# atmega328p_dip28.net
KiCad netlist of a schematic drawn in EAGLE
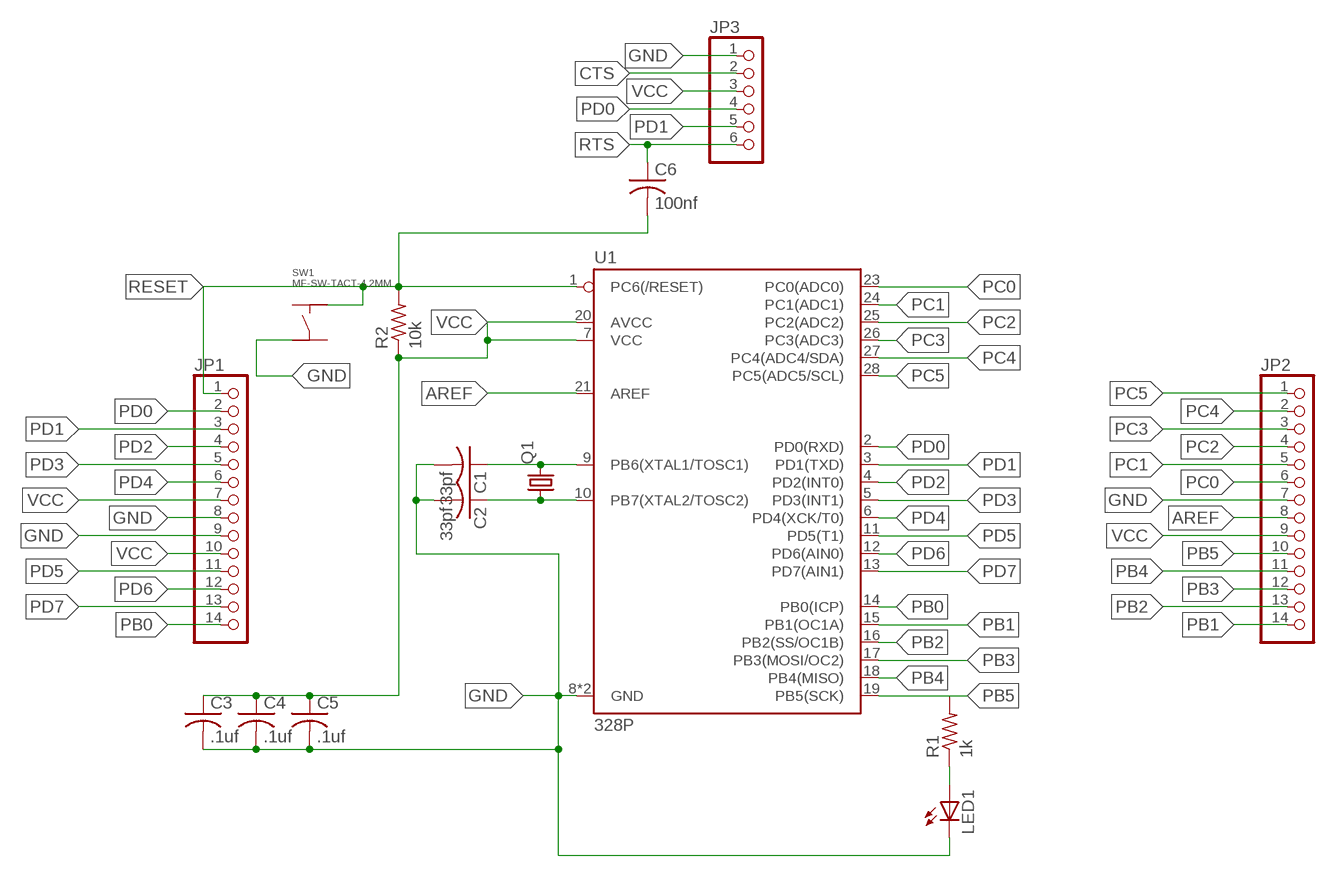
[diagram p0: schematic, sheet 1]

(export (version "E")
  (design (tool "Eeschema 10.0.6"))
  (components
    (comp (ref "C1")
      (value "33pf")
      (footprint "eagle-import:C0603K")
      (libsource (lib "eagle-import") (part "resistor_348_C-USC0603K"))
    )
    (comp (ref "C2")
      (value "33pf")
      (footprint "eagle-import:C0603K")
      (libsource (lib "eagle-import") (part "resistor_348_C-USC0603K"))
    )
    (comp (ref "C3")
      (value ".1uf")
      (footprint "eagle-import:C0603")
      (libsource (lib "eagle-import") (part "C-USC0603"))
    )
    (comp (ref "C4")
      (value ".1uf")
      (footprint "eagle-import:C0603")
      (libsource (lib "eagle-import") (part "C-USC0603"))
    )
    (comp (ref "C5")
      (value ".1uf")
      (footprint "eagle-import:C0603")
      (libsource (lib "eagle-import") (part "C-USC0603"))
    )
    (comp (ref "C6")
      (value "100nf")
      (footprint "eagle-import:C0603")
      (libsource (lib "eagle-import") (part "C-USC0603"))
    )
    (comp (ref "JP1")
      (value "PINHD-1X14-CB")
      (footprint "eagle-import:1X14-CB")
      (libsource (lib "eagle-import") (part "PINHD-1X14-CB"))
    )
    (comp (ref "JP2")
      (value "PINHD-1X14-CB")
      (footprint "eagle-import:1X14-CB")
      (libsource (lib "eagle-import") (part "PINHD-1X14-CB"))
    )
    (comp (ref "JP3")
      (value "PINHD-1X6")
      (footprint "eagle-import:1X06")
      (libsource (lib "eagle-import") (part "PINHD-1X6"))
    )
    (comp (ref "LED1")
      (value "LEDCHIP-LED0805")
      (footprint "eagle-import:CHIP-LED0805")
      (libsource (lib "eagle-import") (part "LEDCHIP-LED0805"))
    )
    (comp (ref "Q1")
      (value "CRYSTALCTS406")
      (footprint "eagle-import:CTS406")
      (libsource (lib "eagle-import") (part "CRYSTALCTS406"))
    )
    (comp (ref "R1")
      (value "1k")
      (footprint "eagle-import:R0603")
      (libsource (lib "eagle-import") (part "R-US_R0603"))
    )
    (comp (ref "R2")
      (value "10k")
      (footprint "eagle-import:R0603")
      (libsource (lib "eagle-import") (part "R-US_R0603"))
    )
    (comp (ref "SW1")
      (value "MF-SW-TACT-4.2MM")
      (footprint "eagle-import:MF_SWITCHES_TACT4.2MM")
      (fields (field (name "HOUSEPART") "YES"))
      (libsource (lib "eagle-import") (part "MF_SWITCHES_TACT_4.2MM"))
    )
    (comp (ref "U1")
      (value "328P")
      (footprint "eagle-import:DIP28")
      (libsource (lib "eagle-import") (part "ATMEGA328P_PDIP"))
    )
  )
  (nets
    (net (code "1") (name "AREF") (class "Default")
      (node (ref "JP2") (pin "8") (pinfunction "8_8") (pintype "passive"))
      (node (ref "U1") (pin "21") (pinfunction "AREF_21") (pintype "bidirectional"))
    )
    (net (code "2") (name "CTS") (class "Default")
      (node (ref "JP3") (pin "2") (pinfunction "2_2") (pintype "passive"))
    )
    (net (code "3") (name "GND") (class "Default")
      (node (ref "C1") (pin "2") (pinfunction "2_2") (pintype "passive"))
      (node (ref "C2") (pin "2") (pinfunction "2_2") (pintype "passive"))
      (node (ref "C3") (pin "2") (pinfunction "2_2") (pintype "passive"))
      (node (ref "C4") (pin "2") (pinfunction "2_2") (pintype "passive"))
      (node (ref "C5") (pin "2") (pinfunction "2_2") (pintype "passive"))
      (node (ref "JP1") (pin "8") (pinfunction "8_8") (pintype "passive"))
      (node (ref "JP1") (pin "9") (pinfunction "9_9") (pintype "passive"))
      (node (ref "JP2") (pin "7") (pinfunction "7_7") (pintype "passive"))
      (node (ref "JP3") (pin "1") (pinfunction "1_1") (pintype "passive"))
      (node (ref "LED1") (pin "C") (pinfunction "C_C") (pintype "passive"))
      (node (ref "SW1") (pin "P$3") (pinfunction "P$3_P$3") (pintype "bidirectional"))
      (node (ref "U1") (pin "22") (pinfunction "GND_22") (pintype "bidirectional"))
      (node (ref "U1") (pin "8") (pinfunction "GND_8") (pintype "bidirectional"))
    )
    (net (code "4") (name "Net-(LED1-PadA)") (class "Default")
      (node (ref "LED1") (pin "A") (pinfunction "A_A") (pintype "passive"))
      (node (ref "R1") (pin "1") (pinfunction "1_1") (pintype "passive"))
    )
    (net (code "5") (name "Net-(Q1-2)") (class "Default")
      (node (ref "C1") (pin "1") (pinfunction "1_1") (pintype "passive"))
      (node (ref "Q1") (pin "3") (pinfunction "2_3") (pintype "passive"))
      (node (ref "U1") (pin "9") (pinfunction "PB6(XTAL1/TOSC1)_9") (pintype "bidirectional"))
    )
    (net (code "6") (name "Net-(U1-PB7(XTAL2{slash}TOSC2))") (class "Default")
      (node (ref "C2") (pin "1") (pinfunction "1_1") (pintype "passive"))
      (node (ref "Q1") (pin "1") (pinfunction "1_1") (pintype "passive"))
      (node (ref "U1") (pin "10") (pinfunction "PB7(XTAL2/TOSC2)_10") (pintype "bidirectional"))
    )
    (net (code "7") (name "PB0") (class "Default")
      (node (ref "JP1") (pin "14") (pinfunction "14_14") (pintype "passive"))
      (node (ref "U1") (pin "14") (pinfunction "PB0(ICP)_14") (pintype "bidirectional"))
    )
    (net (code "8") (name "PB1") (class "Default")
      (node (ref "JP2") (pin "14") (pinfunction "14_14") (pintype "passive"))
      (node (ref "U1") (pin "15") (pinfunction "PB1(OC1A)_15") (pintype "bidirectional"))
    )
    (net (code "9") (name "PB2") (class "Default")
      (node (ref "JP2") (pin "13") (pinfunction "13_13") (pintype "passive"))
      (node (ref "U1") (pin "16") (pinfunction "PB2(SS/OC1B)_16") (pintype "bidirectional"))
    )
    (net (code "10") (name "PB3") (class "Default")
      (node (ref "JP2") (pin "12") (pinfunction "12_12") (pintype "passive"))
      (node (ref "U1") (pin "17") (pinfunction "PB3(MOSI/OC2)_17") (pintype "bidirectional"))
    )
    (net (code "11") (name "PB4") (class "Default")
      (node (ref "JP2") (pin "11") (pinfunction "11_11") (pintype "passive"))
      (node (ref "U1") (pin "18") (pinfunction "PB4(MISO)_18") (pintype "bidirectional"))
    )
    (net (code "12") (name "PB5") (class "Default")
      (node (ref "JP2") (pin "10") (pinfunction "10_10") (pintype "passive"))
      (node (ref "R1") (pin "2") (pinfunction "2_2") (pintype "passive"))
      (node (ref "U1") (pin "19") (pinfunction "PB5(SCK)_19") (pintype "bidirectional"))
    )
    (net (code "13") (name "PC0") (class "Default")
      (node (ref "JP2") (pin "6") (pinfunction "6_6") (pintype "passive"))
      (node (ref "U1") (pin "23") (pinfunction "PC0(ADC0)_23") (pintype "bidirectional"))
    )
    (net (code "14") (name "PC1") (class "Default")
      (node (ref "JP2") (pin "5") (pinfunction "5_5") (pintype "passive"))
      (node (ref "U1") (pin "24") (pinfunction "PC1(ADC1)_24") (pintype "bidirectional"))
    )
    (net (code "15") (name "PC2") (class "Default")
      (node (ref "JP2") (pin "4") (pinfunction "4_4") (pintype "passive"))
      (node (ref "U1") (pin "25") (pinfunction "PC2(ADC2)_25") (pintype "bidirectional"))
    )
    (net (code "16") (name "PC3") (class "Default")
      (node (ref "JP2") (pin "3") (pinfunction "3_3") (pintype "passive"))
      (node (ref "U1") (pin "26") (pinfunction "PC3(ADC3)_26") (pintype "bidirectional"))
    )
    (net (code "17") (name "PC4") (class "Default")
      (node (ref "JP2") (pin "2") (pinfunction "2_2") (pintype "passive"))
      (node (ref "U1") (pin "27") (pinfunction "PC4(ADC4/SDA)_27") (pintype "bidirectional"))
    )
    (net (code "18") (name "PC5") (class "Default")
      (node (ref "JP2") (pin "1") (pinfunction "1_1") (pintype "passive"))
      (node (ref "U1") (pin "28") (pinfunction "PC5(ADC5/SCL)_28") (pintype "bidirectional"))
    )
    (net (code "19") (name "PD0") (class "Default")
      (node (ref "JP1") (pin "2") (pinfunction "2_2") (pintype "passive"))
      (node (ref "JP3") (pin "4") (pinfunction "4_4") (pintype "passive"))
      (node (ref "U1") (pin "2") (pinfunction "PD0(RXD)_2") (pintype "bidirectional"))
    )
    (net (code "20") (name "PD1") (class "Default")
      (node (ref "JP1") (pin "3") (pinfunction "3_3") (pintype "passive"))
      (node (ref "JP3") (pin "5") (pinfunction "5_5") (pintype "passive"))
      (node (ref "U1") (pin "3") (pinfunction "PD1(TXD)_3") (pintype "bidirectional"))
    )
    (net (code "21") (name "PD2") (class "Default")
      (node (ref "JP1") (pin "4") (pinfunction "4_4") (pintype "passive"))
      (node (ref "U1") (pin "4") (pinfunction "PD2(INT0)_4") (pintype "bidirectional"))
    )
    (net (code "22") (name "PD3") (class "Default")
      (node (ref "JP1") (pin "5") (pinfunction "5_5") (pintype "passive"))
      (node (ref "U1") (pin "5") (pinfunction "PD3(INT1)_5") (pintype "bidirectional"))
    )
    (net (code "23") (name "PD4") (class "Default")
      (node (ref "JP1") (pin "6") (pinfunction "6_6") (pintype "passive"))
      (node (ref "U1") (pin "6") (pinfunction "PD4(XCK/T0)_6") (pintype "bidirectional"))
    )
    (net (code "24") (name "PD5") (class "Default")
      (node (ref "JP1") (pin "11") (pinfunction "11_11") (pintype "passive"))
      (node (ref "U1") (pin "11") (pinfunction "PD5(T1)_11") (pintype "bidirectional"))
    )
    (net (code "25") (name "PD6") (class "Default")
      (node (ref "JP1") (pin "12") (pinfunction "12_12") (pintype "passive"))
      (node (ref "U1") (pin "12") (pinfunction "PD6(AIN0)_12") (pintype "bidirectional"))
    )
    (net (code "26") (name "PD7") (class "Default")
      (node (ref "JP1") (pin "13") (pinfunction "13_13") (pintype "passive"))
      (node (ref "U1") (pin "13") (pinfunction "PD7(AIN1)_13") (pintype "bidirectional"))
    )
    (net (code "27") (name "RESET") (class "Default")
      (node (ref "C6") (pin "2") (pinfunction "2_2") (pintype "passive"))
      (node (ref "JP1") (pin "1") (pinfunction "1_1") (pintype "passive"))
      (node (ref "R2") (pin "2") (pinfunction "2_2") (pintype "passive"))
      (node (ref "SW1") (pin "P$2") (pinfunction "P$2_P$2") (pintype "bidirectional"))
      (node (ref "U1") (pin "1") (pinfunction "PC6(/RESET)_1") (pintype "bidirectional"))
    )
    (net (code "28") (name "RTS") (class "Default")
      (node (ref "C6") (pin "1") (pinfunction "1_1") (pintype "passive"))
      (node (ref "JP3") (pin "6") (pinfunction "6_6") (pintype "passive"))
    )
    (net (code "29") (name "VCC") (class "Default")
      (node (ref "C3") (pin "1") (pinfunction "1_1") (pintype "passive"))
      (node (ref "C4") (pin "1") (pinfunction "1_1") (pintype "passive"))
      (node (ref "C5") (pin "1") (pinfunction "1_1") (pintype "passive"))
      (node (ref "JP1") (pin "10") (pinfunction "10_10") (pintype "passive"))
      (node (ref "JP1") (pin "7") (pinfunction "7_7") (pintype "passive"))
      (node (ref "JP2") (pin "9") (pinfunction "9_9") (pintype "passive"))
      (node (ref "JP3") (pin "3") (pinfunction "3_3") (pintype "passive"))
      (node (ref "R2") (pin "1") (pinfunction "1_1") (pintype "passive"))
      (node (ref "U1") (pin "20") (pinfunction "AVCC_20") (pintype "bidirectional"))
      (node (ref "U1") (pin "7") (pinfunction "VCC_7") (pintype "bidirectional"))
    )
    (net (code "30") (name "unconnected-(SW1-PadP$1)") (class "Default")
      (node (ref "SW1") (pin "P$1") (pinfunction "P$1_P$1") (pintype "bidirectional"))
    )
    (net (code "31") (name "unconnected-(SW1-PadP$4)") (class "Default")
      (node (ref "SW1") (pin "P$4") (pinfunction "P$4_P$4") (pintype "bidirectional"))
    )
  )
)
